# Brduino-MCU-Main.net
KiCad netlist of a schematic drawn in Altium Designer
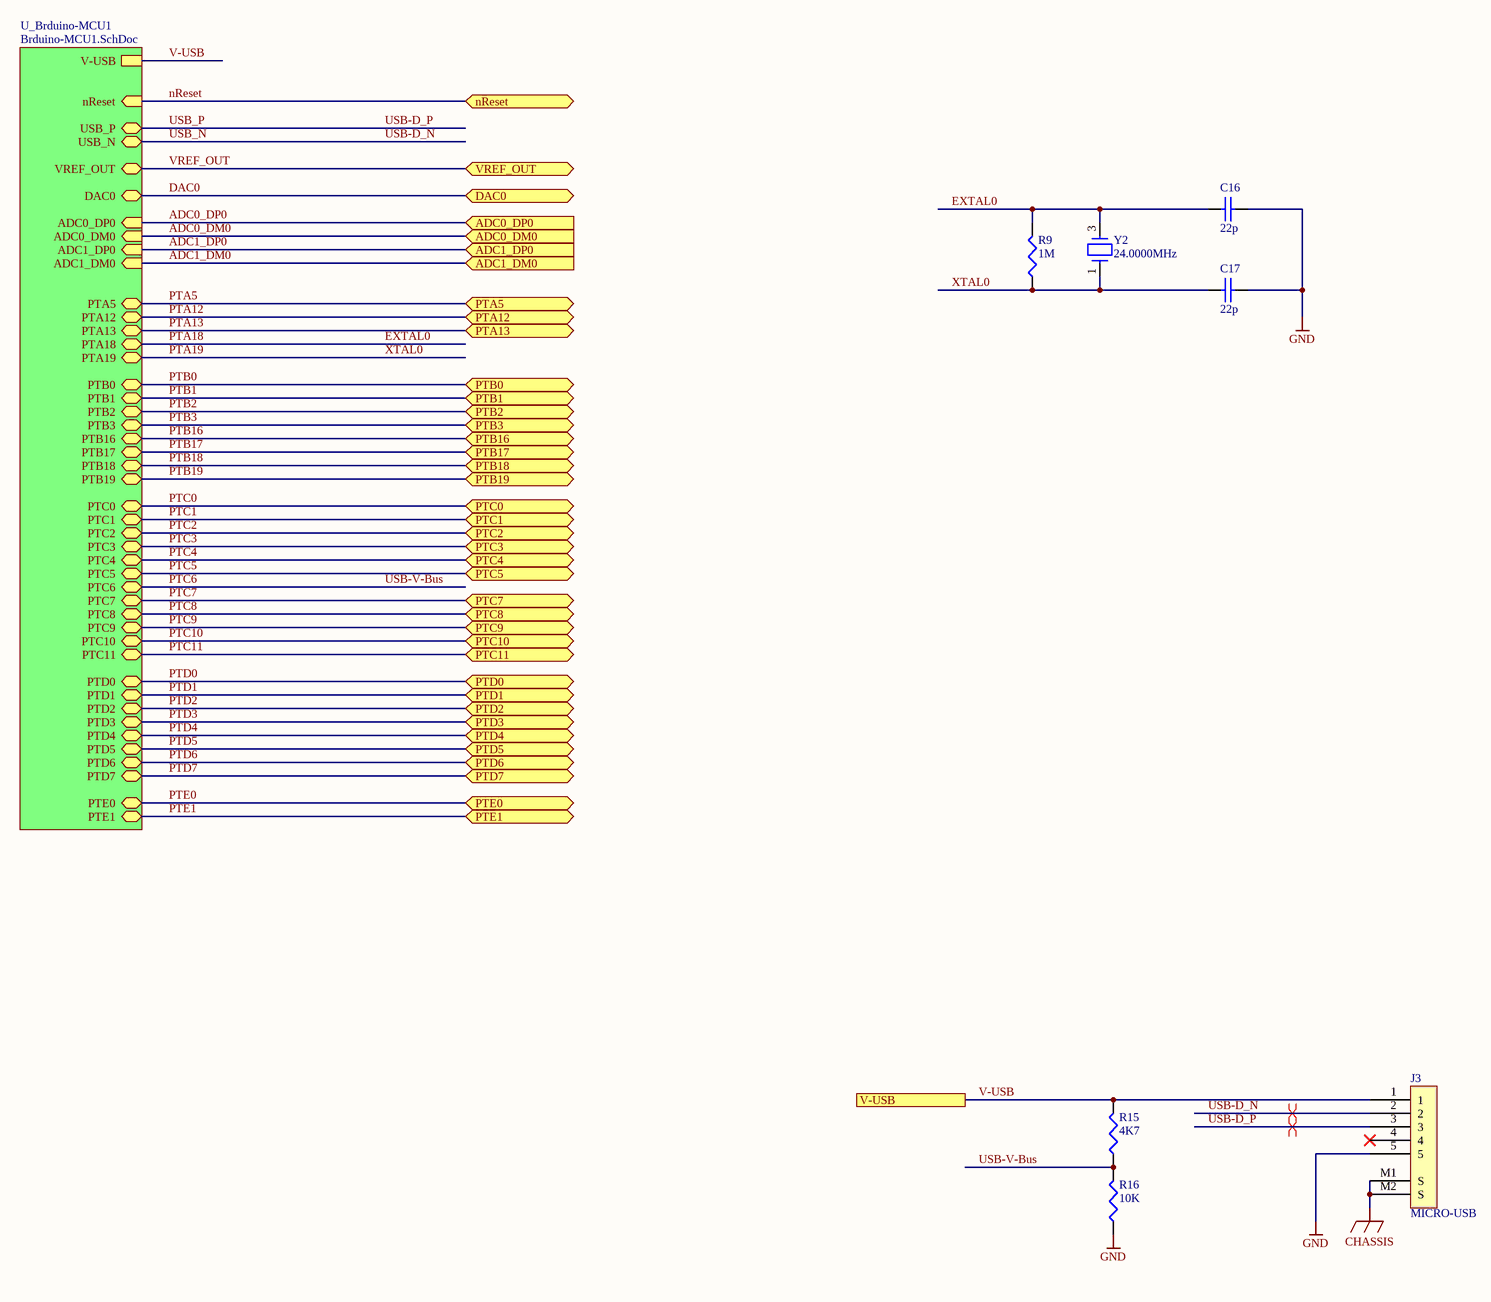
[diagram p0: Brduino-MCU-Main.SchDoc]

(export (version "E")
  (design (tool "Eeschema 10.0.6"))
  (components
    (comp (ref "C16") (value "22p") (footprint "C0402") (libsource (lib "SchLib1") (part "CAP")))
    (comp (ref "C17") (value "22p") (footprint "C0402") (libsource (lib "SchLib1") (part "CAP")))
    (comp (ref "J3")
      (value "MICRO-USB")
      (footprint "Molex-0565790519")
      (fields (field (name "MFR") "GCT"))
      (libsource (lib "SchLib1") (part "MICRO-USB"))
    )
    (comp (ref "R9") (value "1M") (footprint "R0402") (libsource (lib "SchLib1") (part "RES1A")))
    (comp (ref "R15") (value "4K7") (footprint "R0402") (libsource (lib "SchLib1") (part "RES1A")))
    (comp (ref "R16") (value "10K") (footprint "R0402") (libsource (lib "SchLib1") (part "RES1A")))
    (comp (ref "Y2")
      (value "24.0000MHz")
      (footprint "EPSON-XTAL6 3.2mm x 5mm 4pin")
      (fields (field (name "MFR") "EPSON"))
      (libsource (lib "SchLib1") (part "CRYSTAL-5X3.2"))
    )
  )
  (nets
    (net (code "6") (name "/EXTAL0") (class "Default")
      (node (ref "C16") (pin "1") (pinfunction "1_1") (pintype "passive"))
      (node (ref "R9") (pin "2") (pinfunction "2_2") (pintype "passive"))
      (node (ref "Y2") (pin "3") (pinfunction "3_3") (pintype "passive"))
    )
    (net (code "10") (name "/PTA19") (class "Default")
      (node (ref "C17") (pin "1") (pinfunction "1_1") (pintype "passive"))
      (node (ref "R9") (pin "1") (pinfunction "1_1") (pintype "passive"))
      (node (ref "Y2") (pin "1") (pinfunction "1_1") (pintype "passive"))
    )
    (net (code "25") (name "/PTC6") (class "Default")
      (node (ref "R15") (pin "1") (pinfunction "1_1") (pintype "passive"))
      (node (ref "R16") (pin "2") (pinfunction "2_2") (pintype "passive"))
    )
    (net (code "41") (name "/USB-D_N") (class "Default")
      (node (ref "J3") (pin "2") (pinfunction "2_2") (pintype "passive"))
    )
    (net (code "42") (name "/USB-D_P") (class "Default")
      (node (ref "J3") (pin "3") (pinfunction "3_3") (pintype "passive"))
    )
    (net (code "43") (name "/V-USB") (class "Default")
      (node (ref "J3") (pin "1") (pinfunction "1_1") (pintype "passive"))
      (node (ref "R15") (pin "2") (pinfunction "2_2") (pintype "passive"))
    )
    (net (code "46") (name "CHASSIS") (class "Default")
      (node (ref "J3") (pin "M1") (pinfunction "S_M1") (pintype "passive"))
      (node (ref "J3") (pin "M2") (pinfunction "S_M2") (pintype "passive"))
    )
    (net (code "47") (name "GND") (class "Default")
      (node (ref "C16") (pin "2") (pinfunction "2_2") (pintype "passive"))
      (node (ref "C17") (pin "2") (pinfunction "2_2") (pintype "passive"))
      (node (ref "J3") (pin "5") (pinfunction "5_5") (pintype "passive"))
      (node (ref "R16") (pin "1") (pinfunction "1_1") (pintype "passive"))
    )
    (net (code "48") (name "unconnected-(J3-Pad4)") (class "Default")
      (node (ref "J3") (pin "4") (pinfunction "4_4") (pintype "passive+no_connect"))
    )
  )
)
